# FET-Driver-Modul.net
KiCad netlist of a schematic drawn in EAGLE
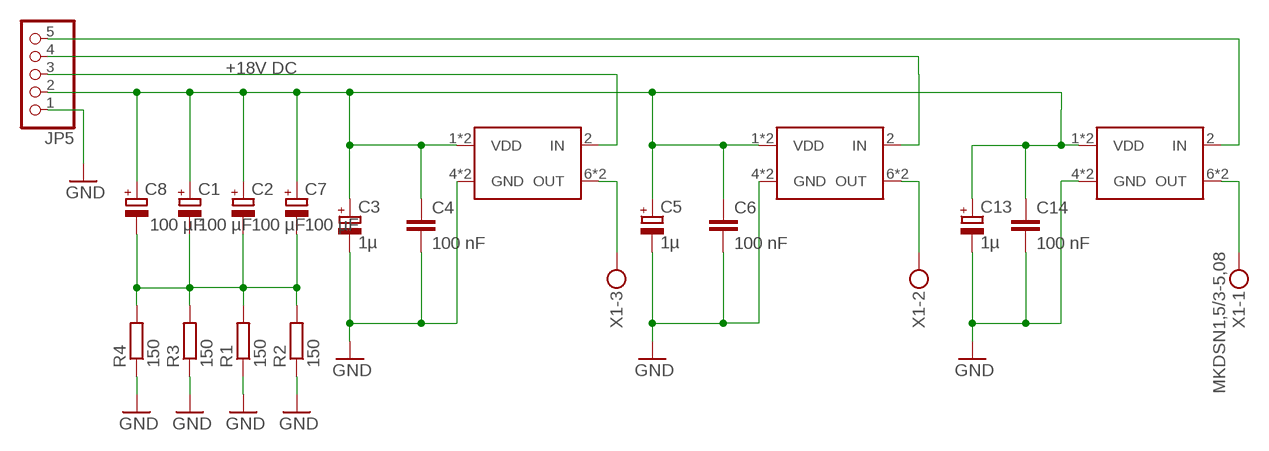
[diagram p0: schematic, sheet 1]

(export (version "E")
  (design (tool "Eeschema 10.0.6"))
  (components
    (comp (ref "C1")
      (value "100 µF")
      (footprint "eagle-import:E2,5-7")
      (libsource (lib "eagle-import") (part "CPOL-EUE2.5-7"))
    )
    (comp (ref "C2")
      (value "100 µF")
      (footprint "eagle-import:E2,5-7")
      (libsource (lib "eagle-import") (part "CPOL-EUE2.5-7"))
    )
    (comp (ref "C3")
      (value "1µ")
      (footprint "eagle-import:E5-8,5")
      (libsource (lib "eagle-import") (part "CPOL-EUE5-8.5"))
    )
    (comp (ref "C4")
      (value "100 nF")
      (footprint "eagle-import:C0603")
      (libsource (lib "eagle-import") (part "C-EUC0603"))
    )
    (comp (ref "C5")
      (value "1µ")
      (footprint "eagle-import:E5-8,5")
      (libsource (lib "eagle-import") (part "CPOL-EUE5-8.5"))
    )
    (comp (ref "C6")
      (value "100 nF")
      (footprint "eagle-import:C0603")
      (libsource (lib "eagle-import") (part "C-EUC0603"))
    )
    (comp (ref "C7")
      (value "100 µF")
      (footprint "eagle-import:E2,5-7")
      (libsource (lib "eagle-import") (part "CPOL-EUE2.5-7"))
    )
    (comp (ref "C8")
      (value "100 µF")
      (footprint "eagle-import:E2,5-7")
      (libsource (lib "eagle-import") (part "CPOL-EUE2.5-7"))
    )
    (comp (ref "C13")
      (value "1µ")
      (footprint "eagle-import:E5-8,5")
      (libsource (lib "eagle-import") (part "CPOL-EUE5-8.5"))
    )
    (comp (ref "C14")
      (value "100 nF")
      (footprint "eagle-import:C0603")
      (libsource (lib "eagle-import") (part "C-EUC0603"))
    )
    (comp (ref "JP5")
      (value "PINHD-1X5")
      (footprint "eagle-import:1X05")
      (libsource (lib "eagle-import") (part "PINHD-1X5"))
    )
    (comp (ref "R1")
      (value "150")
      (footprint "eagle-import:0411_15")
      (libsource (lib "eagle-import") (part "R-EU_0411/15"))
    )
    (comp (ref "R2")
      (value "150")
      (footprint "eagle-import:0411_15")
      (libsource (lib "eagle-import") (part "R-EU_0411/15"))
    )
    (comp (ref "R3")
      (value "150")
      (footprint "eagle-import:0411_15")
      (libsource (lib "eagle-import") (part "R-EU_0411/15"))
    )
    (comp (ref "R4")
      (value "150")
      (footprint "eagle-import:0411_15")
      (libsource (lib "eagle-import") (part "R-EU_0411/15"))
    )
    (comp (ref "U$3")
      (value "MCP1407MCP1407-DIL08")
      (footprint "eagle-import:DIL-08")
      (libsource (lib "eagle-import") (part "MCP1407MCP1407-DIL08"))
    )
    (comp (ref "U$4")
      (value "MCP1407MCP1407-DIL08")
      (footprint "eagle-import:DIL-08")
      (libsource (lib "eagle-import") (part "MCP1407MCP1407-DIL08"))
    )
    (comp (ref "U$5")
      (value "MCP1407MCP1407-DIL08")
      (footprint "eagle-import:DIL-08")
      (libsource (lib "eagle-import") (part "MCP1407MCP1407-DIL08"))
    )
    (comp (ref "X1")
      (value "MKDSN1,5/3-5,08")
      (footprint "eagle-import:MKDSN1,5_3-5,08")
      (libsource (lib "eagle-import") (part "MKDSN1,5/3-5,08"))
    )
  )
  (nets
    (net (code "1") (name "GND") (class "Default")
      (node (ref "C13") (pin "-") (pinfunction "-_-") (pintype "passive"))
      (node (ref "C14") (pin "2") (pinfunction "2_2") (pintype "passive"))
      (node (ref "C3") (pin "-") (pinfunction "-_-") (pintype "passive"))
      (node (ref "C4") (pin "2") (pinfunction "2_2") (pintype "passive"))
      (node (ref "C5") (pin "-") (pinfunction "-_-") (pintype "passive"))
      (node (ref "C6") (pin "2") (pinfunction "2_2") (pintype "passive"))
      (node (ref "JP5") (pin "1") (pinfunction "1_1") (pintype "passive"))
      (node (ref "R1") (pin "1") (pinfunction "1_1") (pintype "passive"))
      (node (ref "R2") (pin "1") (pinfunction "1_1") (pintype "passive"))
      (node (ref "R3") (pin "1") (pinfunction "1_1") (pintype "passive"))
      (node (ref "R4") (pin "1") (pinfunction "1_1") (pintype "passive"))
      (node (ref "U$3") (pin "4") (pinfunction "GND_4") (pintype "bidirectional"))
      (node (ref "U$3") (pin "5") (pinfunction "GND_5") (pintype "bidirectional"))
      (node (ref "U$4") (pin "4") (pinfunction "GND_4") (pintype "bidirectional"))
      (node (ref "U$4") (pin "5") (pinfunction "GND_5") (pintype "bidirectional"))
      (node (ref "U$5") (pin "4") (pinfunction "GND_4") (pintype "bidirectional"))
      (node (ref "U$5") (pin "5") (pinfunction "GND_5") (pintype "bidirectional"))
    )
    (net (code "2") (name "Net-(C1-Pad+)") (class "Default")
      (node (ref "C1") (pin "+") (pinfunction "+_+") (pintype "passive"))
      (node (ref "C13") (pin "+") (pinfunction "+_+") (pintype "passive"))
      (node (ref "C14") (pin "1") (pinfunction "1_1") (pintype "passive"))
      (node (ref "C2") (pin "+") (pinfunction "+_+") (pintype "passive"))
      (node (ref "C3") (pin "+") (pinfunction "+_+") (pintype "passive"))
      (node (ref "C4") (pin "1") (pinfunction "1_1") (pintype "passive"))
      (node (ref "C5") (pin "+") (pinfunction "+_+") (pintype "passive"))
      (node (ref "C6") (pin "1") (pinfunction "1_1") (pintype "passive"))
      (node (ref "C7") (pin "+") (pinfunction "+_+") (pintype "passive"))
      (node (ref "C8") (pin "+") (pinfunction "+_+") (pintype "passive"))
      (node (ref "JP5") (pin "2") (pinfunction "2_2") (pintype "passive"))
      (node (ref "U$3") (pin "1") (pinfunction "VDD_1") (pintype "bidirectional"))
      (node (ref "U$3") (pin "8") (pinfunction "VDD_8") (pintype "bidirectional"))
      (node (ref "U$4") (pin "1") (pinfunction "VDD_1") (pintype "bidirectional"))
      (node (ref "U$4") (pin "8") (pinfunction "VDD_8") (pintype "bidirectional"))
      (node (ref "U$5") (pin "1") (pinfunction "VDD_1") (pintype "bidirectional"))
      (node (ref "U$5") (pin "8") (pinfunction "VDD_8") (pintype "bidirectional"))
    )
    (net (code "3") (name "Net-(C1-Pad-)") (class "Default")
      (node (ref "C1") (pin "-") (pinfunction "-_-") (pintype "passive"))
      (node (ref "C2") (pin "-") (pinfunction "-_-") (pintype "passive"))
      (node (ref "C7") (pin "-") (pinfunction "-_-") (pintype "passive"))
      (node (ref "C8") (pin "-") (pinfunction "-_-") (pintype "passive"))
      (node (ref "R1") (pin "2") (pinfunction "2_2") (pintype "passive"))
      (node (ref "R2") (pin "2") (pinfunction "2_2") (pintype "passive"))
      (node (ref "R3") (pin "2") (pinfunction "2_2") (pintype "passive"))
      (node (ref "R4") (pin "2") (pinfunction "2_2") (pintype "passive"))
    )
    (net (code "4") (name "Net-(U$3-IN)") (class "Default")
      (node (ref "JP5") (pin "3") (pinfunction "3_3") (pintype "passive"))
      (node (ref "U$3") (pin "2") (pinfunction "IN_2") (pintype "bidirectional"))
    )
    (net (code "5") (name "Net-(U$4-IN)") (class "Default")
      (node (ref "JP5") (pin "4") (pinfunction "4_4") (pintype "passive"))
      (node (ref "U$4") (pin "2") (pinfunction "IN_2") (pintype "bidirectional"))
    )
    (net (code "6") (name "Net-(U$5-IN)") (class "Default")
      (node (ref "JP5") (pin "5") (pinfunction "5_5") (pintype "passive"))
      (node (ref "U$5") (pin "2") (pinfunction "IN_2") (pintype "bidirectional"))
    )
    (net (code "7") (name "Net-(X1A-KL)") (class "Default")
      (node (ref "U$5") (pin "6") (pinfunction "OUT_6") (pintype "bidirectional"))
      (node (ref "U$5") (pin "7") (pinfunction "OUT_7") (pintype "bidirectional"))
      (node (ref "X1") (pin "1") (pinfunction "KL_1") (pintype "passive"))
    )
    (net (code "8") (name "Net-(X1B-KL)") (class "Default")
      (node (ref "U$4") (pin "6") (pinfunction "OUT_6") (pintype "bidirectional"))
      (node (ref "U$4") (pin "7") (pinfunction "OUT_7") (pintype "bidirectional"))
      (node (ref "X1") (pin "2") (pinfunction "KL_2") (pintype "passive"))
    )
    (net (code "9") (name "Net-(X1C-KL)") (class "Default")
      (node (ref "U$3") (pin "6") (pinfunction "OUT_6") (pintype "bidirectional"))
      (node (ref "U$3") (pin "7") (pinfunction "OUT_7") (pintype "bidirectional"))
      (node (ref "X1") (pin "3") (pinfunction "KL_3") (pintype "passive"))
    )
  )
)
